# MCU.net
KiCad netlist of a schematic drawn in Altium Designer
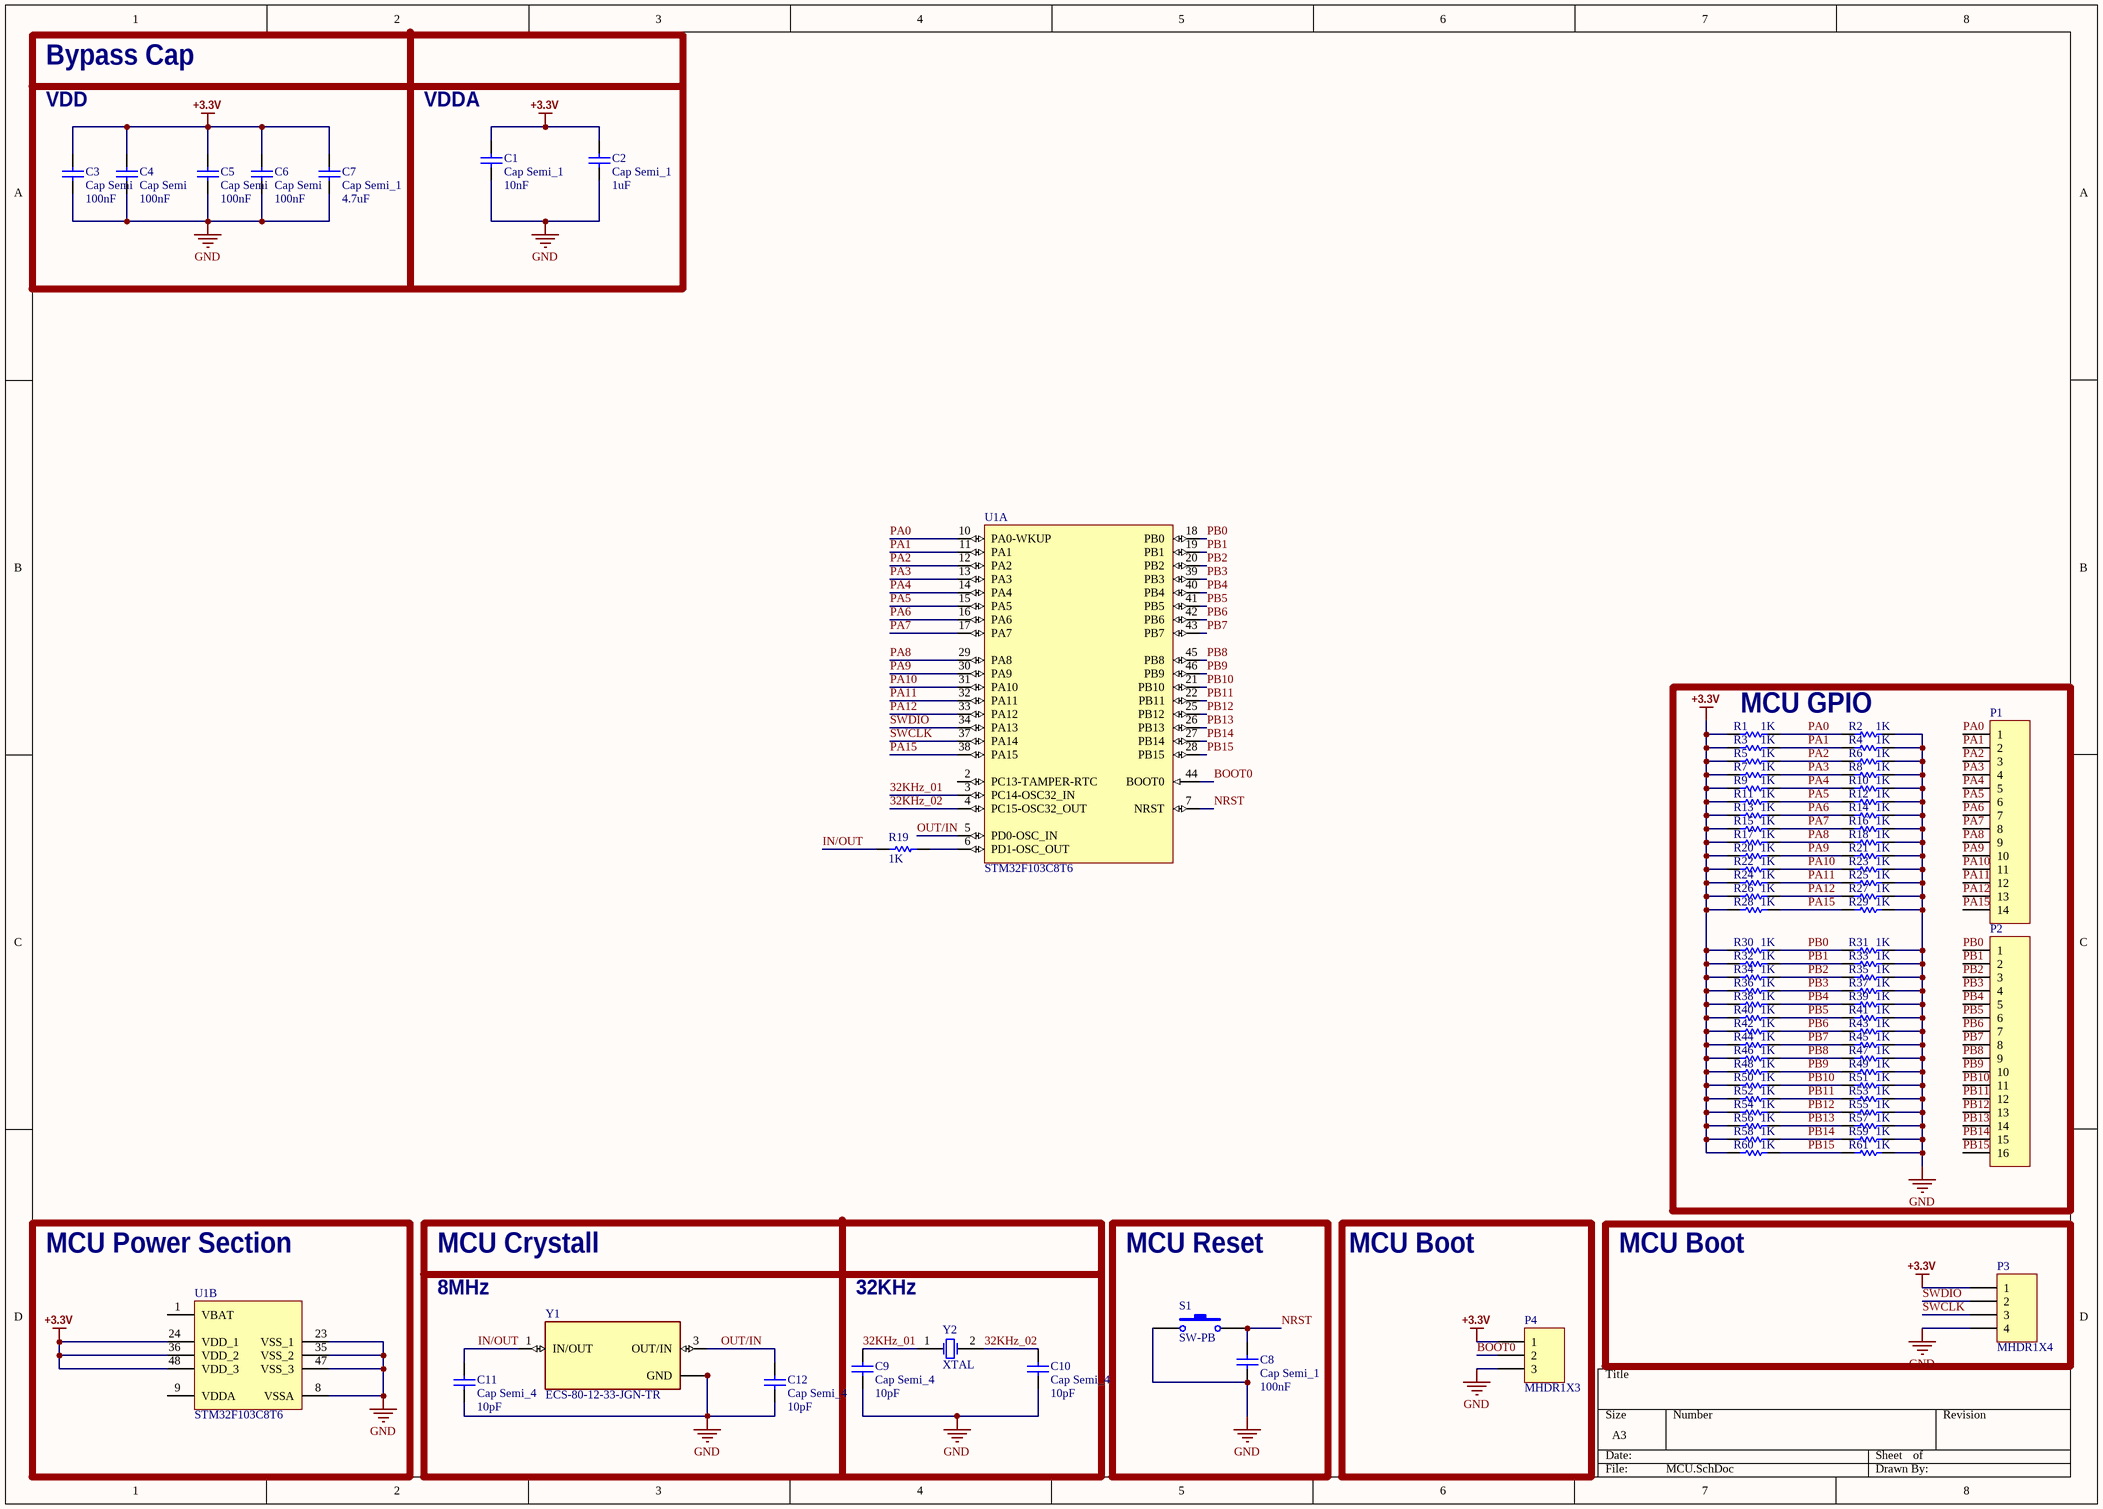
[diagram p0: MCU.SchDoc]

(export (version "E")
  (design (tool "Eeschema 10.0.6"))
  (components
    (comp (ref "C1")
      (value "Cap Semi_1")
      (footprint "1608[0603]cap")
      (description "Capacitor (Semiconductor SIM Model)")
      (fields (field (name "ALTIUM_VALUE") "10nF") (field (name "PUBLISHER") "Altium Limited"))
      (libsource (lib "smartmcu") (part "Cap Semi_1_2"))
    )
    (comp (ref "C2")
      (value "Cap Semi_1")
      (footprint "1608[0603]cap")
      (description "Capacitor (Semiconductor SIM Model)")
      (fields (field (name "ALTIUM_VALUE") "1uF") (field (name "PUBLISHER") "Altium Limited"))
      (libsource (lib "smartmcu") (part "Cap Semi_1_3"))
    )
    (comp (ref "C3")
      (value "Cap Semi")
      (footprint "1608[0603]cap")
      (description "Capacitor (Semiconductor SIM Model)")
      (fields (field (name "ALTIUM_VALUE") "100nF") (field (name "PUBLISHER") "Altium Limited"))
      (libsource (lib "smartmcu") (part "Cap Semi"))
    )
    (comp (ref "C4")
      (value "Cap Semi")
      (footprint "1608[0603]cap")
      (description "Capacitor (Semiconductor SIM Model)")
      (fields (field (name "ALTIUM_VALUE") "100nF") (field (name "PUBLISHER") "Altium Limited"))
      (libsource (lib "smartmcu") (part "Cap Semi"))
    )
    (comp (ref "C5")
      (value "Cap Semi")
      (footprint "1608[0603]cap")
      (description "Capacitor (Semiconductor SIM Model)")
      (fields (field (name "ALTIUM_VALUE") "100nF") (field (name "PUBLISHER") "Altium Limited"))
      (libsource (lib "smartmcu") (part "Cap Semi"))
    )
    (comp (ref "C6")
      (value "Cap Semi")
      (footprint "1608[0603]cap")
      (description "Capacitor (Semiconductor SIM Model)")
      (fields (field (name "ALTIUM_VALUE") "100nF") (field (name "PUBLISHER") "Altium Limited"))
      (libsource (lib "smartmcu") (part "Cap Semi"))
    )
    (comp (ref "C7")
      (value "Cap Semi_1")
      (footprint "1608[0603]cap")
      (description "Capacitor (Semiconductor SIM Model)")
      (fields (field (name "ALTIUM_VALUE") "4.7uF") (field (name "PUBLISHER") "Altium Limited"))
      (libsource (lib "smartmcu") (part "Cap Semi_1_1"))
    )
    (comp (ref "C8")
      (value "Cap Semi_1")
      (footprint "1608[0603]cap")
      (description "Capacitor (Semiconductor SIM Model)")
      (fields (field (name "ALTIUM_VALUE") "100nF") (field (name "PUBLISHER") "Altium Limited"))
      (libsource (lib "smartmcu") (part "Cap Semi_1"))
    )
    (comp (ref "C9")
      (value "Cap Semi_4")
      (footprint "0402cap")
      (description "Capacitor (Semiconductor SIM Model)")
      (fields (field (name "ALTIUM_VALUE") "10pF") (field (name "PUBLISHER") "Altium Limited"))
      (libsource (lib "smartmcu") (part "Cap Semi_4"))
    )
    (comp (ref "C10")
      (value "Cap Semi_4")
      (footprint "0402cap")
      (description "Capacitor (Semiconductor SIM Model)")
      (fields (field (name "ALTIUM_VALUE") "10pF") (field (name "PUBLISHER") "Altium Limited"))
      (libsource (lib "smartmcu") (part "Cap Semi_4"))
    )
    (comp (ref "C11")
      (value "Cap Semi_4")
      (footprint "0402cap")
      (description "Capacitor (Semiconductor SIM Model)")
      (fields (field (name "ALTIUM_VALUE") "10pF") (field (name "PUBLISHER") "Altium Limited"))
      (libsource (lib "smartmcu") (part "Cap Semi_4"))
    )
    (comp (ref "C12")
      (value "Cap Semi_4")
      (footprint "0402cap")
      (description "Capacitor (Semiconductor SIM Model)")
      (fields (field (name "ALTIUM_VALUE") "10pF") (field (name "PUBLISHER") "Altium Limited"))
      (libsource (lib "smartmcu") (part "Cap Semi_4"))
    )
    (comp (ref "P1")
      (value "Header 14")
      (footprint "My_1X14")
      (description "Header, 14-Pin")
      (fields (field (name "ASID PART NUMBER") "Header 14-AS"))
      (libsource (lib "Mylib+Rev+4") (part "Header 14"))
    )
    (comp (ref "P2")
      (value "Header 16")
      (footprint "My_1X16")
      (description "Header, 16-Pin")
      (fields (field (name "ASID PART NUMBER") "Header 16-AS"))
      (libsource (lib "Mylib+Rev+4") (part "Header 16"))
    )
    (comp (ref "P3")
      (value "MHDR1X4")
      (footprint "MHDR1X4body")
      (description "Header, 4-Pin")
      (fields (field (name "PUBLISHER") "Altium Limited"))
      (libsource (lib "smartmcu") (part "MHDR1X4"))
    )
    (comp (ref "P4")
      (value "MHDR1X3")
      (footprint "MHDR1X3body")
      (description "Header, 3-Pin")
      (fields (field (name "PUBLISHER") "Altium Limited"))
      (libsource (lib "smartmcu") (part "MHDR1X3"))
    )
    (comp (ref "R1")
      (value "1K")
      (footprint "MY_0603")
      (description "Standard resistor")
      (fields (field (name "ASID PART NUMBER") "Res-AS"))
      (libsource (lib "Mylib+Rev+4") (part "Res"))
    )
    (comp (ref "R2")
      (value "1K")
      (footprint "MY_0603")
      (description "Standard resistor")
      (fields (field (name "ASID PART NUMBER") "Res-AS"))
      (libsource (lib "Mylib+Rev+4") (part "Res"))
    )
    (comp (ref "R3")
      (value "1K")
      (footprint "MY_0603")
      (description "Standard resistor")
      (fields (field (name "ASID PART NUMBER") "Res-AS"))
      (libsource (lib "Mylib+Rev+4") (part "Res"))
    )
    (comp (ref "R4")
      (value "1K")
      (footprint "MY_0603")
      (description "Standard resistor")
      (fields (field (name "ASID PART NUMBER") "Res-AS"))
      (libsource (lib "Mylib+Rev+4") (part "Res"))
    )
    (comp (ref "R5")
      (value "1K")
      (footprint "MY_0603")
      (description "Standard resistor")
      (fields (field (name "ASID PART NUMBER") "Res-AS"))
      (libsource (lib "Mylib+Rev+4") (part "Res"))
    )
    (comp (ref "R6")
      (value "1K")
      (footprint "MY_0603")
      (description "Standard resistor")
      (fields (field (name "ASID PART NUMBER") "Res-AS"))
      (libsource (lib "Mylib+Rev+4") (part "Res"))
    )
    (comp (ref "R7")
      (value "1K")
      (footprint "MY_0603")
      (description "Standard resistor")
      (fields (field (name "ASID PART NUMBER") "Res-AS"))
      (libsource (lib "Mylib+Rev+4") (part "Res"))
    )
    (comp (ref "R8")
      (value "1K")
      (footprint "MY_0603")
      (description "Standard resistor")
      (fields (field (name "ASID PART NUMBER") "Res-AS"))
      (libsource (lib "Mylib+Rev+4") (part "Res"))
    )
    (comp (ref "R9")
      (value "1K")
      (footprint "MY_0603")
      (description "Standard resistor")
      (fields (field (name "ASID PART NUMBER") "Res-AS"))
      (libsource (lib "Mylib+Rev+4") (part "Res"))
    )
    (comp (ref "R10")
      (value "1K")
      (footprint "MY_0603")
      (description "Standard resistor")
      (fields (field (name "ASID PART NUMBER") "Res-AS"))
      (libsource (lib "Mylib+Rev+4") (part "Res"))
    )
    (comp (ref "R11")
      (value "1K")
      (footprint "MY_0603")
      (description "Standard resistor")
      (fields (field (name "ASID PART NUMBER") "Res-AS"))
      (libsource (lib "Mylib+Rev+4") (part "Res"))
    )
    (comp (ref "R12")
      (value "1K")
      (footprint "MY_0603")
      (description "Standard resistor")
      (fields (field (name "ASID PART NUMBER") "Res-AS"))
      (libsource (lib "Mylib+Rev+4") (part "Res"))
    )
    (comp (ref "R13")
      (value "1K")
      (footprint "MY_0603")
      (description "Standard resistor")
      (fields (field (name "ASID PART NUMBER") "Res-AS"))
      (libsource (lib "Mylib+Rev+4") (part "Res"))
    )
    (comp (ref "R14")
      (value "1K")
      (footprint "MY_0603")
      (description "Standard resistor")
      (fields (field (name "ASID PART NUMBER") "Res-AS"))
      (libsource (lib "Mylib+Rev+4") (part "Res"))
    )
    (comp (ref "R15")
      (value "1K")
      (footprint "MY_0603")
      (description "Standard resistor")
      (fields (field (name "ASID PART NUMBER") "Res-AS"))
      (libsource (lib "Mylib+Rev+4") (part "Res"))
    )
    (comp (ref "R16")
      (value "1K")
      (footprint "MY_0603")
      (description "Standard resistor")
      (fields (field (name "ASID PART NUMBER") "Res-AS"))
      (libsource (lib "Mylib+Rev+4") (part "Res"))
    )
    (comp (ref "R17")
      (value "1K")
      (footprint "MY_0603")
      (description "Standard resistor")
      (fields (field (name "ASID PART NUMBER") "Res-AS"))
      (libsource (lib "Mylib+Rev+4") (part "Res"))
    )
    (comp (ref "R18")
      (value "1K")
      (footprint "MY_0603")
      (description "Standard resistor")
      (fields (field (name "ASID PART NUMBER") "Res-AS"))
      (libsource (lib "Mylib+Rev+4") (part "Res"))
    )
    (comp (ref "R19")
      (value "1K")
      (footprint "MY_0603")
      (description "Standard resistor")
      (fields (field (name "ASID PART NUMBER") "Res-AS"))
      (libsource (lib "smartmcu") (part "Res"))
    )
    (comp (ref "R20")
      (value "1K")
      (footprint "MY_0603")
      (description "Standard resistor")
      (fields (field (name "ASID PART NUMBER") "Res-AS"))
      (libsource (lib "Mylib+Rev+4") (part "Res"))
    )
    (comp (ref "R21")
      (value "1K")
      (footprint "MY_0603")
      (description "Standard resistor")
      (fields (field (name "ASID PART NUMBER") "Res-AS"))
      (libsource (lib "Mylib+Rev+4") (part "Res"))
    )
    (comp (ref "R22")
      (value "1K")
      (footprint "MY_0603")
      (description "Standard resistor")
      (fields (field (name "ASID PART NUMBER") "Res-AS"))
      (libsource (lib "Mylib+Rev+4") (part "Res"))
    )
    (comp (ref "R23")
      (value "1K")
      (footprint "MY_0603")
      (description "Standard resistor")
      (fields (field (name "ASID PART NUMBER") "Res-AS"))
      (libsource (lib "Mylib+Rev+4") (part "Res"))
    )
    (comp (ref "R24")
      (value "1K")
      (footprint "MY_0603")
      (description "Standard resistor")
      (fields (field (name "ASID PART NUMBER") "Res-AS"))
      (libsource (lib "Mylib+Rev+4") (part "Res"))
    )
    (comp (ref "R25")
      (value "1K")
      (footprint "MY_0603")
      (description "Standard resistor")
      (fields (field (name "ASID PART NUMBER") "Res-AS"))
      (libsource (lib "Mylib+Rev+4") (part "Res"))
    )
    (comp (ref "R26")
      (value "1K")
      (footprint "MY_0603")
      (description "Standard resistor")
      (fields (field (name "ASID PART NUMBER") "Res-AS"))
      (libsource (lib "Mylib+Rev+4") (part "Res"))
    )
    (comp (ref "R27")
      (value "1K")
      (footprint "MY_0603")
      (description "Standard resistor")
      (fields (field (name "ASID PART NUMBER") "Res-AS"))
      (libsource (lib "Mylib+Rev+4") (part "Res"))
    )
    (comp (ref "R28")
      (value "1K")
      (footprint "MY_0603")
      (description "Standard resistor")
      (fields (field (name "ASID PART NUMBER") "Res-AS"))
      (libsource (lib "Mylib+Rev+4") (part "Res"))
    )
    (comp (ref "R29")
      (value "1K")
      (footprint "MY_0603")
      (description "Standard resistor")
      (fields (field (name "ASID PART NUMBER") "Res-AS"))
      (libsource (lib "Mylib+Rev+4") (part "Res"))
    )
    (comp (ref "R30")
      (value "1K")
      (footprint "MY_0603")
      (description "Standard resistor")
      (fields (field (name "ASID PART NUMBER") "Res-AS"))
      (libsource (lib "Mylib+Rev+4") (part "Res"))
    )
    (comp (ref "R31")
      (value "1K")
      (footprint "MY_0603")
      (description "Standard resistor")
      (fields (field (name "ASID PART NUMBER") "Res-AS"))
      (libsource (lib "Mylib+Rev+4") (part "Res"))
    )
    (comp (ref "R32")
      (value "1K")
      (footprint "MY_0603")
      (description "Standard resistor")
      (fields (field (name "ASID PART NUMBER") "Res-AS"))
      (libsource (lib "Mylib+Rev+4") (part "Res"))
    )
    (comp (ref "R33")
      (value "1K")
      (footprint "MY_0603")
      (description "Standard resistor")
      (fields (field (name "ASID PART NUMBER") "Res-AS"))
      (libsource (lib "Mylib+Rev+4") (part "Res"))
    )
    (comp (ref "R34")
      (value "1K")
      (footprint "MY_0603")
      (description "Standard resistor")
      (fields (field (name "ASID PART NUMBER") "Res-AS"))
      (libsource (lib "Mylib+Rev+4") (part "Res"))
    )
    (comp (ref "R35")
      (value "1K")
      (footprint "MY_0603")
      (description "Standard resistor")
      (fields (field (name "ASID PART NUMBER") "Res-AS"))
      (libsource (lib "Mylib+Rev+4") (part "Res"))
    )
    (comp (ref "R36")
      (value "1K")
      (footprint "MY_0603")
      (description "Standard resistor")
      (fields (field (name "ASID PART NUMBER") "Res-AS"))
      (libsource (lib "Mylib+Rev+4") (part "Res"))
    )
    (comp (ref "R37")
      (value "1K")
      (footprint "MY_0603")
      (description "Standard resistor")
      (fields (field (name "ASID PART NUMBER") "Res-AS"))
      (libsource (lib "Mylib+Rev+4") (part "Res"))
    )
    (comp (ref "R38")
      (value "1K")
      (footprint "MY_0603")
      (description "Standard resistor")
      (fields (field (name "ASID PART NUMBER") "Res-AS"))
      (libsource (lib "Mylib+Rev+4") (part "Res"))
    )
    (comp (ref "R39")
      (value "1K")
      (footprint "MY_0603")
      (description "Standard resistor")
      (fields (field (name "ASID PART NUMBER") "Res-AS"))
      (libsource (lib "Mylib+Rev+4") (part "Res"))
    )
    (comp (ref "R40")
      (value "1K")
      (footprint "MY_0603")
      (description "Standard resistor")
      (fields (field (name "ASID PART NUMBER") "Res-AS"))
      (libsource (lib "Mylib+Rev+4") (part "Res"))
    )
    (comp (ref "R41")
      (value "1K")
      (footprint "MY_0603")
      (description "Standard resistor")
      (fields (field (name "ASID PART NUMBER") "Res-AS"))
      (libsource (lib "Mylib+Rev+4") (part "Res"))
    )
    (comp (ref "R42")
      (value "1K")
      (footprint "MY_0603")
      (description "Standard resistor")
      (fields (field (name "ASID PART NUMBER") "Res-AS"))
      (libsource (lib "Mylib+Rev+4") (part "Res"))
    )
    (comp (ref "R43")
      (value "1K")
      (footprint "MY_0603")
      (description "Standard resistor")
      (fields (field (name "ASID PART NUMBER") "Res-AS"))
      (libsource (lib "Mylib+Rev+4") (part "Res"))
    )
    (comp (ref "R44")
      (value "1K")
      (footprint "MY_0603")
      (description "Standard resistor")
      (fields (field (name "ASID PART NUMBER") "Res-AS"))
      (libsource (lib "Mylib+Rev+4") (part "Res"))
    )
    (comp (ref "R45")
      (value "1K")
      (footprint "MY_0603")
      (description "Standard resistor")
      (fields (field (name "ASID PART NUMBER") "Res-AS"))
      (libsource (lib "Mylib+Rev+4") (part "Res"))
    )
    (comp (ref "R46")
      (value "1K")
      (footprint "MY_0603")
      (description "Standard resistor")
      (fields (field (name "ASID PART NUMBER") "Res-AS"))
      (libsource (lib "Mylib+Rev+4") (part "Res"))
    )
    (comp (ref "R47")
      (value "1K")
      (footprint "MY_0603")
      (description "Standard resistor")
      (fields (field (name "ASID PART NUMBER") "Res-AS"))
      (libsource (lib "Mylib+Rev+4") (part "Res"))
    )
    (comp (ref "R48")
      (value "1K")
      (footprint "MY_0603")
      (description "Standard resistor")
      (fields (field (name "ASID PART NUMBER") "Res-AS"))
      (libsource (lib "Mylib+Rev+4") (part "Res"))
    )
    (comp (ref "R49")
      (value "1K")
      (footprint "MY_0603")
      (description "Standard resistor")
      (fields (field (name "ASID PART NUMBER") "Res-AS"))
      (libsource (lib "Mylib+Rev+4") (part "Res"))
    )
    (comp (ref "R50")
      (value "1K")
      (footprint "MY_0603")
      (description "Standard resistor")
      (fields (field (name "ASID PART NUMBER") "Res-AS"))
      (libsource (lib "Mylib+Rev+4") (part "Res"))
    )
    (comp (ref "R51")
      (value "1K")
      (footprint "MY_0603")
      (description "Standard resistor")
      (fields (field (name "ASID PART NUMBER") "Res-AS"))
      (libsource (lib "Mylib+Rev+4") (part "Res"))
    )
    (comp (ref "R52")
      (value "1K")
      (footprint "MY_0603")
      (description "Standard resistor")
      (fields (field (name "ASID PART NUMBER") "Res-AS"))
      (libsource (lib "Mylib+Rev+4") (part "Res"))
    )
    (comp (ref "R53")
      (value "1K")
      (footprint "MY_0603")
      (description "Standard resistor")
      (fields (field (name "ASID PART NUMBER") "Res-AS"))
      (libsource (lib "Mylib+Rev+4") (part "Res"))
    )
    (comp (ref "R54")
      (value "1K")
      (footprint "MY_0603")
      (description "Standard resistor")
      (fields (field (name "ASID PART NUMBER") "Res-AS"))
      (libsource (lib "Mylib+Rev+4") (part "Res"))
    )
    (comp (ref "R55")
      (value "1K")
      (footprint "MY_0603")
      (description "Standard resistor")
      (fields (field (name "ASID PART NUMBER") "Res-AS"))
      (libsource (lib "Mylib+Rev+4") (part "Res"))
    )
    (comp (ref "R56")
      (value "1K")
      (footprint "MY_0603")
      (description "Standard resistor")
      (fields (field (name "ASID PART NUMBER") "Res-AS"))
      (libsource (lib "Mylib+Rev+4") (part "Res"))
    )
    (comp (ref "R57")
      (value "1K")
      (footprint "MY_0603")
      (description "Standard resistor")
      (fields (field (name "ASID PART NUMBER") "Res-AS"))
      (libsource (lib "Mylib+Rev+4") (part "Res"))
    )
    (comp (ref "R58")
      (value "1K")
      (footprint "MY_0603")
      (description "Standard resistor")
      (fields (field (name "ASID PART NUMBER") "Res-AS"))
      (libsource (lib "Mylib+Rev+4") (part "Res"))
    )
    (comp (ref "R59")
      (value "1K")
      (footprint "MY_0603")
      (description "Standard resistor")
      (fields (field (name "ASID PART NUMBER") "Res-AS"))
      (libsource (lib "Mylib+Rev+4") (part "Res"))
    )
    (comp (ref "R60")
      (value "1K")
      (footprint "MY_0603")
      (description "Standard resistor")
      (fields (field (name "ASID PART NUMBER") "Res-AS"))
      (libsource (lib "Mylib+Rev+4") (part "Res"))
    )
    (comp (ref "R61")
      (value "1K")
      (footprint "MY_0603")
      (description "Standard resistor")
      (fields (field (name "ASID PART NUMBER") "Res-AS"))
      (libsource (lib "Mylib+Rev+4") (part "Res"))
    )
    (comp (ref "S1")
      (value "SW-PB")
      (footprint "SPST-2_body")
      (description "Switch")
      (fields (field (name "PUBLISHER") "Altium Limited"))
      (libsource (lib "smartmcu") (part "SW-PB"))
    )
    (comp (ref "U1")
      (value "STM32F103C8T6")
      (footprint "STM-LQFP48_N")
      (libsource (lib "smartmcu") (part "STM32F103C8T6"))
    )
    (comp (ref "Y1")
      (value "ECS-80-12-33-JGN-TR")
      (footprint "8MHZCrystall")
      (description "8MHz Â±20ppm Crystal 12pF 400 Ohms 4-SMD, No Lead")
      (fields
        (field (name "MF") "ECS Inc.")
        (field (name "BUYPART") "https://www.snapeda.com/parts/ECS-80-12-33-JGN-TR/ECS%20Inc./view-part/4477300/?ref=eda")
      )
      (libsource (lib "smartmcu") (part "ECS-80-12-33-JGN-TR"))
    )
    (comp (ref "Y2")
      (value "XTAL")
      (footprint "32768")
      (description "Crystal Oscillator")
      (fields (field (name "PUBLISHER") "Altium Limited"))
      (libsource (lib "smartmcu") (part "XTAL"))
    )
  )
  (nets
    (net (code "1") (name "+3.3V") (class "Default")
      (node (ref "C1") (pin "2") (pinfunction "2_2") (pintype "passive"))
      (node (ref "C2") (pin "2") (pinfunction "2_2") (pintype "passive"))
      (node (ref "C3") (pin "2") (pinfunction "2_2") (pintype "passive"))
      (node (ref "C4") (pin "2") (pinfunction "2_2") (pintype "passive"))
      (node (ref "C5") (pin "2") (pinfunction "2_2") (pintype "passive"))
      (node (ref "C6") (pin "2") (pinfunction "2_2") (pintype "passive"))
      (node (ref "C7") (pin "2") (pinfunction "2_2") (pintype "passive"))
      (node (ref "P3") (pin "1") (pinfunction "1_1") (pintype "passive"))
      (node (ref "P4") (pin "1") (pinfunction "1_1") (pintype "passive"))
      (node (ref "R1") (pin "1") (pinfunction "1_1") (pintype "passive"))
      (node (ref "R11") (pin "1") (pinfunction "1_1") (pintype "passive"))
      (node (ref "R13") (pin "1") (pinfunction "1_1") (pintype "passive"))
      (node (ref "R15") (pin "1") (pinfunction "1_1") (pintype "passive"))
      (node (ref "R17") (pin "1") (pinfunction "1_1") (pintype "passive"))
      (node (ref "R20") (pin "1") (pinfunction "1_1") (pintype "passive"))
      (node (ref "R22") (pin "1") (pinfunction "1_1") (pintype "passive"))
      (node (ref "R24") (pin "1") (pinfunction "1_1") (pintype "passive"))
      (node (ref "R26") (pin "1") (pinfunction "1_1") (pintype "passive"))
      (node (ref "R28") (pin "1") (pinfunction "1_1") (pintype "passive"))
      (node (ref "R3") (pin "1") (pinfunction "1_1") (pintype "passive"))
      (node (ref "R30") (pin "1") (pinfunction "1_1") (pintype "passive"))
      (node (ref "R32") (pin "1") (pinfunction "1_1") (pintype "passive"))
      (node (ref "R34") (pin "1") (pinfunction "1_1") (pintype "passive"))
      (node (ref "R36") (pin "1") (pinfunction "1_1") (pintype "passive"))
      (node (ref "R38") (pin "1") (pinfunction "1_1") (pintype "passive"))
      (node (ref "R40") (pin "1") (pinfunction "1_1") (pintype "passive"))
      (node (ref "R42") (pin "1") (pinfunction "1_1") (pintype "passive"))
      (node (ref "R44") (pin "1") (pinfunction "1_1") (pintype "passive"))
      (node (ref "R46") (pin "1") (pinfunction "1_1") (pintype "passive"))
      (node (ref "R48") (pin "1") (pinfunction "1_1") (pintype "passive"))
      (node (ref "R5") (pin "1") (pinfunction "1_1") (pintype "passive"))
      (node (ref "R50") (pin "1") (pinfunction "1_1") (pintype "passive"))
      (node (ref "R52") (pin "1") (pinfunction "1_1") (pintype "passive"))
      (node (ref "R54") (pin "1") (pinfunction "1_1") (pintype "passive"))
      (node (ref "R56") (pin "1") (pinfunction "1_1") (pintype "passive"))
      (node (ref "R58") (pin "1") (pinfunction "1_1") (pintype "passive"))
      (node (ref "R60") (pin "1") (pinfunction "1_1") (pintype "passive"))
      (node (ref "R7") (pin "1") (pinfunction "1_1") (pintype "passive"))
      (node (ref "R9") (pin "1") (pinfunction "1_1") (pintype "passive"))
      (node (ref "U1") (pin "24") (pinfunction "VDD_1_24") (pintype "power_in"))
      (node (ref "U1") (pin "36") (pinfunction "VDD_2_36") (pintype "power_in"))
      (node (ref "U1") (pin "48") (pinfunction "VDD_3_48") (pintype "power_in"))
    )
    (net (code "2") (name "/32KHz_01") (class "Default")
      (node (ref "C9") (pin "2") (pinfunction "2_2") (pintype "passive"))
      (node (ref "U1") (pin "3") (pinfunction "PC14-OSC32_IN_3") (pintype "bidirectional"))
      (node (ref "Y2") (pin "1") (pinfunction "OSC1_1") (pintype "passive"))
    )
    (net (code "3") (name "/32KHz_02") (class "Default")
      (node (ref "C10") (pin "2") (pinfunction "2_2") (pintype "passive"))
      (node (ref "U1") (pin "4") (pinfunction "PC15-OSC32_OUT_4") (pintype "bidirectional"))
      (node (ref "Y2") (pin "2") (pinfunction "OSC2_2") (pintype "passive"))
    )
    (net (code "4") (name "/BOOT0") (class "Default")
      (node (ref "P4") (pin "2") (pinfunction "2_2") (pintype "passive"))
      (node (ref "U1") (pin "44") (pinfunction "BOOT0_44") (pintype "input"))
    )
    (net (code "5") (name "/IN{slash}OUT") (class "Default")
      (node (ref "C11") (pin "2") (pinfunction "2_2") (pintype "passive"))
      (node (ref "R19") (pin "1") (pinfunction "1_1") (pintype "passive"))
      (node (ref "Y1") (pin "1") (pinfunction "IN/OUT_1") (pintype "bidirectional"))
    )
    (net (code "6") (name "/NRST") (class "Default")
      (node (ref "C8") (pin "2") (pinfunction "2_2") (pintype "passive"))
      (node (ref "S1") (pin "2") (pinfunction "2_2") (pintype "passive"))
      (node (ref "U1") (pin "7") (pinfunction "NRST_7") (pintype "bidirectional"))
    )
    (net (code "7") (name "/OUT{slash}IN") (class "Default")
      (node (ref "C12") (pin "2") (pinfunction "2_2") (pintype "passive"))
      (node (ref "U1") (pin "5") (pinfunction "PD0-OSC_IN_5") (pintype "bidirectional"))
      (node (ref "Y1") (pin "3") (pinfunction "OUT/IN_3") (pintype "bidirectional"))
    )
    (net (code "8") (name "/PA0") (class "Default")
      (node (ref "P1") (pin "1") (pinfunction "1_1") (pintype "passive"))
      (node (ref "R1") (pin "2") (pinfunction "2_2") (pintype "passive"))
      (node (ref "R2") (pin "1") (pinfunction "1_1") (pintype "passive"))
      (node (ref "U1") (pin "10") (pinfunction "PA0-WKUP_10") (pintype "bidirectional"))
    )
    (net (code "9") (name "/PA1") (class "Default")
      (node (ref "P1") (pin "2") (pinfunction "2_2") (pintype "passive"))
      (node (ref "R3") (pin "2") (pinfunction "2_2") (pintype "passive"))
      (node (ref "R4") (pin "1") (pinfunction "1_1") (pintype "passive"))
      (node (ref "U1") (pin "11") (pinfunction "PA1_11") (pintype "bidirectional"))
    )
    (net (code "10") (name "/PA2") (class "Default")
      (node (ref "P1") (pin "3") (pinfunction "3_3") (pintype "passive"))
      (node (ref "R5") (pin "2") (pinfunction "2_2") (pintype "passive"))
      (node (ref "R6") (pin "1") (pinfunction "1_1") (pintype "passive"))
      (node (ref "U1") (pin "12") (pinfunction "PA2_12") (pintype "bidirectional"))
    )
    (net (code "11") (name "/PA3") (class "Default")
      (node (ref "P1") (pin "4") (pinfunction "4_4") (pintype "passive"))
      (node (ref "R7") (pin "2") (pinfunction "2_2") (pintype "passive"))
      (node (ref "R8") (pin "1") (pinfunction "1_1") (pintype "passive"))
      (node (ref "U1") (pin "13") (pinfunction "PA3_13") (pintype "bidirectional"))
    )
    (net (code "12") (name "/PA4") (class "Default")
      (node (ref "P1") (pin "5") (pinfunction "5_5") (pintype "passive"))
      (node (ref "R10") (pin "1") (pinfunction "1_1") (pintype "passive"))
      (node (ref "R9") (pin "2") (pinfunction "2_2") (pintype "passive"))
      (node (ref "U1") (pin "14") (pinfunction "PA4_14") (pintype "bidirectional"))
    )
    (net (code "13") (name "/PA5") (class "Default")
      (node (ref "P1") (pin "6") (pinfunction "6_6") (pintype "passive"))
      (node (ref "R11") (pin "2") (pinfunction "2_2") (pintype "passive"))
      (node (ref "R12") (pin "1") (pinfunction "1_1") (pintype "passive"))
      (node (ref "U1") (pin "15") (pinfunction "PA5_15") (pintype "bidirectional"))
    )
    (net (code "14") (name "/PA6") (class "Default")
      (node (ref "P1") (pin "7") (pinfunction "7_7") (pintype "passive"))
      (node (ref "R13") (pin "2") (pinfunction "2_2") (pintype "passive"))
      (node (ref "R14") (pin "1") (pinfunction "1_1") (pintype "passive"))
      (node (ref "U1") (pin "16") (pinfunction "PA6_16") (pintype "bidirectional"))
    )
    (net (code "15") (name "/PA7") (class "Default")
      (node (ref "P1") (pin "8") (pinfunction "8_8") (pintype "passive"))
      (node (ref "R15") (pin "2") (pinfunction "2_2") (pintype "passive"))
      (node (ref "R16") (pin "1") (pinfunction "1_1") (pintype "passive"))
      (node (ref "U1") (pin "17") (pinfunction "PA7_17") (pintype "bidirectional"))
    )
    (net (code "16") (name "/PA8") (class "Default")
      (node (ref "P1") (pin "9") (pinfunction "9_9") (pintype "passive"))
      (node (ref "R17") (pin "2") (pinfunction "2_2") (pintype "passive"))
      (node (ref "R18") (pin "1") (pinfunction "1_1") (pintype "passive"))
      (node (ref "U1") (pin "29") (pinfunction "PA8_29") (pintype "bidirectional"))
    )
    (net (code "17") (name "/PA9") (class "Default")
      (node (ref "P1") (pin "10") (pinfunction "10_10") (pintype "passive"))
      (node (ref "R20") (pin "2") (pinfunction "2_2") (pintype "passive"))
      (node (ref "R21") (pin "1") (pinfunction "1_1") (pintype "passive"))
      (node (ref "U1") (pin "30") (pinfunction "PA9_30") (pintype "bidirectional"))
    )
    (net (code "18") (name "/PA10") (class "Default")
      (node (ref "P1") (pin "11") (pinfunction "11_11") (pintype "passive"))
      (node (ref "R22") (pin "2") (pinfunction "2_2") (pintype "passive"))
      (node (ref "R23") (pin "1") (pinfunction "1_1") (pintype "passive"))
      (node (ref "U1") (pin "31") (pinfunction "PA10_31") (pintype "bidirectional"))
    )
    (net (code "19") (name "/PA11") (class "Default")
      (node (ref "P1") (pin "12") (pinfunction "12_12") (pintype "passive"))
      (node (ref "R24") (pin "2") (pinfunction "2_2") (pintype "passive"))
      (node (ref "R25") (pin "1") (pinfunction "1_1") (pintype "passive"))
      (node (ref "U1") (pin "32") (pinfunction "PA11_32") (pintype "bidirectional"))
    )
    (net (code "20") (name "/PA12") (class "Default")
      (node (ref "P1") (pin "13") (pinfunction "13_13") (pintype "passive"))
      (node (ref "R26") (pin "2") (pinfunction "2_2") (pintype "passive"))
      (node (ref "R27") (pin "1") (pinfunction "1_1") (pintype "passive"))
      (node (ref "U1") (pin "33") (pinfunction "PA12_33") (pintype "bidirectional"))
    )
    (net (code "21") (name "/PA15") (class "Default")
      (node (ref "P1") (pin "14") (pinfunction "14_14") (pintype "passive"))
      (node (ref "R28") (pin "2") (pinfunction "2_2") (pintype "passive"))
      (node (ref "R29") (pin "1") (pinfunction "1_1") (pintype "passive"))
      (node (ref "U1") (pin "38") (pinfunction "PA15_38") (pintype "bidirectional"))
    )
    (net (code "22") (name "/PB0") (class "Default")
      (node (ref "P2") (pin "1") (pinfunction "1_1") (pintype "passive"))
      (node (ref "R30") (pin "2") (pinfunction "2_2") (pintype "passive"))
      (node (ref "R31") (pin "1") (pinfunction "1_1") (pintype "passive"))
      (node (ref "U1") (pin "18") (pinfunction "PB0_18") (pintype "bidirectional"))
    )
    (net (code "23") (name "/PB1") (class "Default")
      (node (ref "P2") (pin "2") (pinfunction "2_2") (pintype "passive"))
      (node (ref "R32") (pin "2") (pinfunction "2_2") (pintype "passive"))
      (node (ref "R33") (pin "1") (pinfunction "1_1") (pintype "passive"))
      (node (ref "U1") (pin "19") (pinfunction "PB1_19") (pintype "bidirectional"))
    )
    (net (code "24") (name "/PB2") (class "Default")
      (node (ref "P2") (pin "3") (pinfunction "3_3") (pintype "passive"))
      (node (ref "R34") (pin "2") (pinfunction "2_2") (pintype "passive"))
      (node (ref "R35") (pin "1") (pinfunction "1_1") (pintype "passive"))
      (node (ref "U1") (pin "20") (pinfunction "PB2_20") (pintype "bidirectional"))
    )
    (net (code "25") (name "/PB3") (class "Default")
      (node (ref "P2") (pin "4") (pinfunction "4_4") (pintype "passive"))
      (node (ref "R36") (pin "2") (pinfunction "2_2") (pintype "passive"))
      (node (ref "R37") (pin "1") (pinfunction "1_1") (pintype "passive"))
      (node (ref "U1") (pin "39") (pinfunction "PB3_39") (pintype "bidirectional"))
    )
    (net (code "26") (name "/PB4") (class "Default")
      (node (ref "P2") (pin "5") (pinfunction "5_5") (pintype "passive"))
      (node (ref "R38") (pin "2") (pinfunction "2_2") (pintype "passive"))
      (node (ref "R39") (pin "1") (pinfunction "1_1") (pintype "passive"))
      (node (ref "U1") (pin "40") (pinfunction "PB4_40") (pintype "bidirectional"))
    )
    (net (code "27") (name "/PB5") (class "Default")
      (node (ref "P2") (pin "6") (pinfunction "6_6") (pintype "passive"))
      (node (ref "R40") (pin "2") (pinfunction "2_2") (pintype "passive"))
      (node (ref "R41") (pin "1") (pinfunction "1_1") (pintype "passive"))
      (node (ref "U1") (pin "41") (pinfunction "PB5_41") (pintype "bidirectional"))
    )
    (net (code "28") (name "/PB6") (class "Default")
      (node (ref "P2") (pin "7") (pinfunction "7_7") (pintype "passive"))
      (node (ref "R42") (pin "2") (pinfunction "2_2") (pintype "passive"))
      (node (ref "R43") (pin "1") (pinfunction "1_1") (pintype "passive"))
      (node (ref "U1") (pin "42") (pinfunction "PB6_42") (pintype "bidirectional"))
    )
    (net (code "29") (name "/PB7") (class "Default")
      (node (ref "P2") (pin "8") (pinfunction "8_8") (pintype "passive"))
      (node (ref "R44") (pin "2") (pinfunction "2_2") (pintype "passive"))
      (node (ref "R45") (pin "1") (pinfunction "1_1") (pintype "passive"))
      (node (ref "U1") (pin "43") (pinfunction "PB7_43") (pintype "bidirectional"))
    )
    (net (code "30") (name "/PB8") (class "Default")
      (node (ref "P2") (pin "9") (pinfunction "9_9") (pintype "passive"))
      (node (ref "R46") (pin "2") (pinfunction "2_2") (pintype "passive"))
      (node (ref "R47") (pin "1") (pinfunction "1_1") (pintype "passive"))
      (node (ref "U1") (pin "45") (pinfunction "PB8_45") (pintype "bidirectional"))
    )
    (net (code "31") (name "/PB9") (class "Default")
      (node (ref "P2") (pin "10") (pinfunction "10_10") (pintype "passive"))
      (node (ref "R48") (pin "2") (pinfunction "2_2") (pintype "passive"))
      (node (ref "R49") (pin "1") (pinfunction "1_1") (pintype "passive"))
      (node (ref "U1") (pin "46") (pinfunction "PB9_46") (pintype "bidirectional"))
    )
    (net (code "32") (name "/PB10") (class "Default")
      (node (ref "P2") (pin "11") (pinfunction "11_11") (pintype "passive"))
      (node (ref "R50") (pin "2") (pinfunction "2_2") (pintype "passive"))
      (node (ref "R51") (pin "1") (pinfunction "1_1") (pintype "passive"))
      (node (ref "U1") (pin "21") (pinfunction "PB10_21") (pintype "bidirectional"))
    )
    (net (code "33") (name "/PB11") (class "Default")
      (node (ref "P2") (pin "12") (pinfunction "12_12") (pintype "passive"))
      (node (ref "R52") (pin "2") (pinfunction "2_2") (pintype "passive"))
      (node (ref "R53") (pin "1") (pinfunction "1_1") (pintype "passive"))
      (node (ref "U1") (pin "22") (pinfunction "PB11_22") (pintype "bidirectional"))
    )
    (net (code "34") (name "/PB12") (class "Default")
      (node (ref "P2") (pin "13") (pinfunction "13_13") (pintype "passive"))
      (node (ref "R54") (pin "2") (pinfunction "2_2") (pintype "passive"))
      (node (ref "R55") (pin "1") (pinfunction "1_1") (pintype "passive"))
      (node (ref "U1") (pin "25") (pinfunction "PB12_25") (pintype "bidirectional"))
    )
    (net (code "35") (name "/PB13") (class "Default")
      (node (ref "P2") (pin "14") (pinfunction "14_14") (pintype "passive"))
      (node (ref "R56") (pin "2") (pinfunction "2_2") (pintype "passive"))
      (node (ref "R57") (pin "1") (pinfunction "1_1") (pintype "passive"))
      (node (ref "U1") (pin "26") (pinfunction "PB13_26") (pintype "bidirectional"))
    )
    (net (code "36") (name "/PB14") (class "Default")
      (node (ref "P2") (pin "15") (pinfunction "15_15") (pintype "passive"))
      (node (ref "R58") (pin "2") (pinfunction "2_2") (pintype "passive"))
      (node (ref "R59") (pin "1") (pinfunction "1_1") (pintype "passive"))
      (node (ref "U1") (pin "27") (pinfunction "PB14_27") (pintype "bidirectional"))
    )
    (net (code "37") (name "/PB15") (class "Default")
      (node (ref "P2") (pin "16") (pinfunction "16_16") (pintype "passive"))
      (node (ref "R60") (pin "2") (pinfunction "2_2") (pintype "passive"))
      (node (ref "R61") (pin "1") (pinfunction "1_1") (pintype "passive"))
      (node (ref "U1") (pin "28") (pinfunction "PB15_28") (pintype "bidirectional"))
    )
    (net (code "38") (name "/SWCLK") (class "Default")
      (node (ref "P3") (pin "3") (pinfunction "3_3") (pintype "passive"))
      (node (ref "U1") (pin "37") (pinfunction "PA14_37") (pintype "bidirectional"))
    )
    (net (code "39") (name "/SWDIO") (class "Default")
      (node (ref "P3") (pin "2") (pinfunction "2_2") (pintype "passive"))
      (node (ref "U1") (pin "34") (pinfunction "PA13_34") (pintype "bidirectional"))
    )
    (net (code "40") (name "GND") (class "Default")
      (node (ref "C1") (pin "1") (pinfunction "1_1") (pintype "passive"))
      (node (ref "C10") (pin "1") (pinfunction "1_1") (pintype "passive"))
      (node (ref "C11") (pin "1") (pinfunction "1_1") (pintype "passive"))
      (node (ref "C12") (pin "1") (pinfunction "1_1") (pintype "passive"))
      (node (ref "C2") (pin "1") (pinfunction "1_1") (pintype "passive"))
      (node (ref "C3") (pin "1") (pinfunction "1_1") (pintype "passive"))
      (node (ref "C4") (pin "1") (pinfunction "1_1") (pintype "passive"))
      (node (ref "C5") (pin "1") (pinfunction "1_1") (pintype "passive"))
      (node (ref "C6") (pin "1") (pinfunction "1_1") (pintype "passive"))
      (node (ref "C7") (pin "1") (pinfunction "1_1") (pintype "passive"))
      (node (ref "C8") (pin "1") (pinfunction "1_1") (pintype "passive"))
      (node (ref "C9") (pin "1") (pinfunction "1_1") (pintype "passive"))
      (node (ref "P3") (pin "4") (pinfunction "4_4") (pintype "passive"))
      (node (ref "P4") (pin "3") (pinfunction "3_3") (pintype "passive"))
      (node (ref "R10") (pin "2") (pinfunction "2_2") (pintype "passive"))
      (node (ref "R12") (pin "2") (pinfunction "2_2") (pintype "passive"))
      (node (ref "R14") (pin "2") (pinfunction "2_2") (pintype "passive"))
      (node (ref "R16") (pin "2") (pinfunction "2_2") (pintype "passive"))
      (node (ref "R18") (pin "2") (pinfunction "2_2") (pintype "passive"))
      (node (ref "R2") (pin "2") (pinfunction "2_2") (pintype "passive"))
      (node (ref "R21") (pin "2") (pinfunction "2_2") (pintype "passive"))
      (node (ref "R23") (pin "2") (pinfunction "2_2") (pintype "passive"))
      (node (ref "R25") (pin "2") (pinfunction "2_2") (pintype "passive"))
      (node (ref "R27") (pin "2") (pinfunction "2_2") (pintype "passive"))
      (node (ref "R29") (pin "2") (pinfunction "2_2") (pintype "passive"))
      (node (ref "R31") (pin "2") (pinfunction "2_2") (pintype "passive"))
      (node (ref "R33") (pin "2") (pinfunction "2_2") (pintype "passive"))
      (node (ref "R35") (pin "2") (pinfunction "2_2") (pintype "passive"))
      (node (ref "R37") (pin "2") (pinfunction "2_2") (pintype "passive"))
      (node (ref "R39") (pin "2") (pinfunction "2_2") (pintype "passive"))
      (node (ref "R4") (pin "2") (pinfunction "2_2") (pintype "passive"))
      (node (ref "R41") (pin "2") (pinfunction "2_2") (pintype "passive"))
      (node (ref "R43") (pin "2") (pinfunction "2_2") (pintype "passive"))
      (node (ref "R45") (pin "2") (pinfunction "2_2") (pintype "passive"))
      (node (ref "R47") (pin "2") (pinfunction "2_2") (pintype "passive"))
      (node (ref "R49") (pin "2") (pinfunction "2_2") (pintype "passive"))
      (node (ref "R51") (pin "2") (pinfunction "2_2") (pintype "passive"))
      (node (ref "R53") (pin "2") (pinfunction "2_2") (pintype "passive"))
      (node (ref "R55") (pin "2") (pinfunction "2_2") (pintype "passive"))
      (node (ref "R57") (pin "2") (pinfunction "2_2") (pintype "passive"))
      (node (ref "R59") (pin "2") (pinfunction "2_2") (pintype "passive"))
      (node (ref "R6") (pin "2") (pinfunction "2_2") (pintype "passive"))
      (node (ref "R61") (pin "2") (pinfunction "2_2") (pintype "passive"))
      (node (ref "R8") (pin "2") (pinfunction "2_2") (pintype "passive"))
      (node (ref "S1") (pin "1") (pinfunction "1_1") (pintype "passive"))
      (node (ref "U1") (pin "23") (pinfunction "VSS_1_23") (pintype "power_in"))
      (node (ref "U1") (pin "35") (pinfunction "VSS_2_35") (pintype "power_in"))
      (node (ref "U1") (pin "47") (pinfunction "VSS_3_47") (pintype "power_in"))
      (node (ref "U1") (pin "8") (pinfunction "VSSA_8") (pintype "power_in"))
      (node (ref "Y1") (pin "2") (pinfunction "GND_2") (pintype "power_in"))
      (node (ref "Y1") (pin "4") (pinfunction "GND_4") (pintype "power_in"))
    )
    (net (code "41") (name "Net-(U1A-PD1-OSC_OUT)") (class "Default")
      (node (ref "R19") (pin "2") (pinfunction "2_2") (pintype "passive"))
      (node (ref "U1") (pin "6") (pinfunction "PD1-OSC_OUT_6") (pintype "bidirectional"))
    )
    (net (code "42") (name "unconnected-(U1A-PC13-TAMPER-RTC-Pad2)") (class "Default")
      (node (ref "U1") (pin "2") (pinfunction "PC13-TAMPER-RTC_2") (pintype "bidirectional"))
    )
    (net (code "43") (name "unconnected-(U1B-VBAT-Pad1)") (class "Default")
      (node (ref "U1") (pin "1") (pinfunction "VBAT_1") (pintype "power_in"))
    )
    (net (code "44") (name "unconnected-(U1B-VDDA-Pad9)") (class "Default")
      (node (ref "U1") (pin "9") (pinfunction "VDDA_9") (pintype "power_in"))
    )
  )
)
